# TK104_Pulsbegrenser_Eurorack.net
KiCad netlist of a schematic drawn in Altium Designer
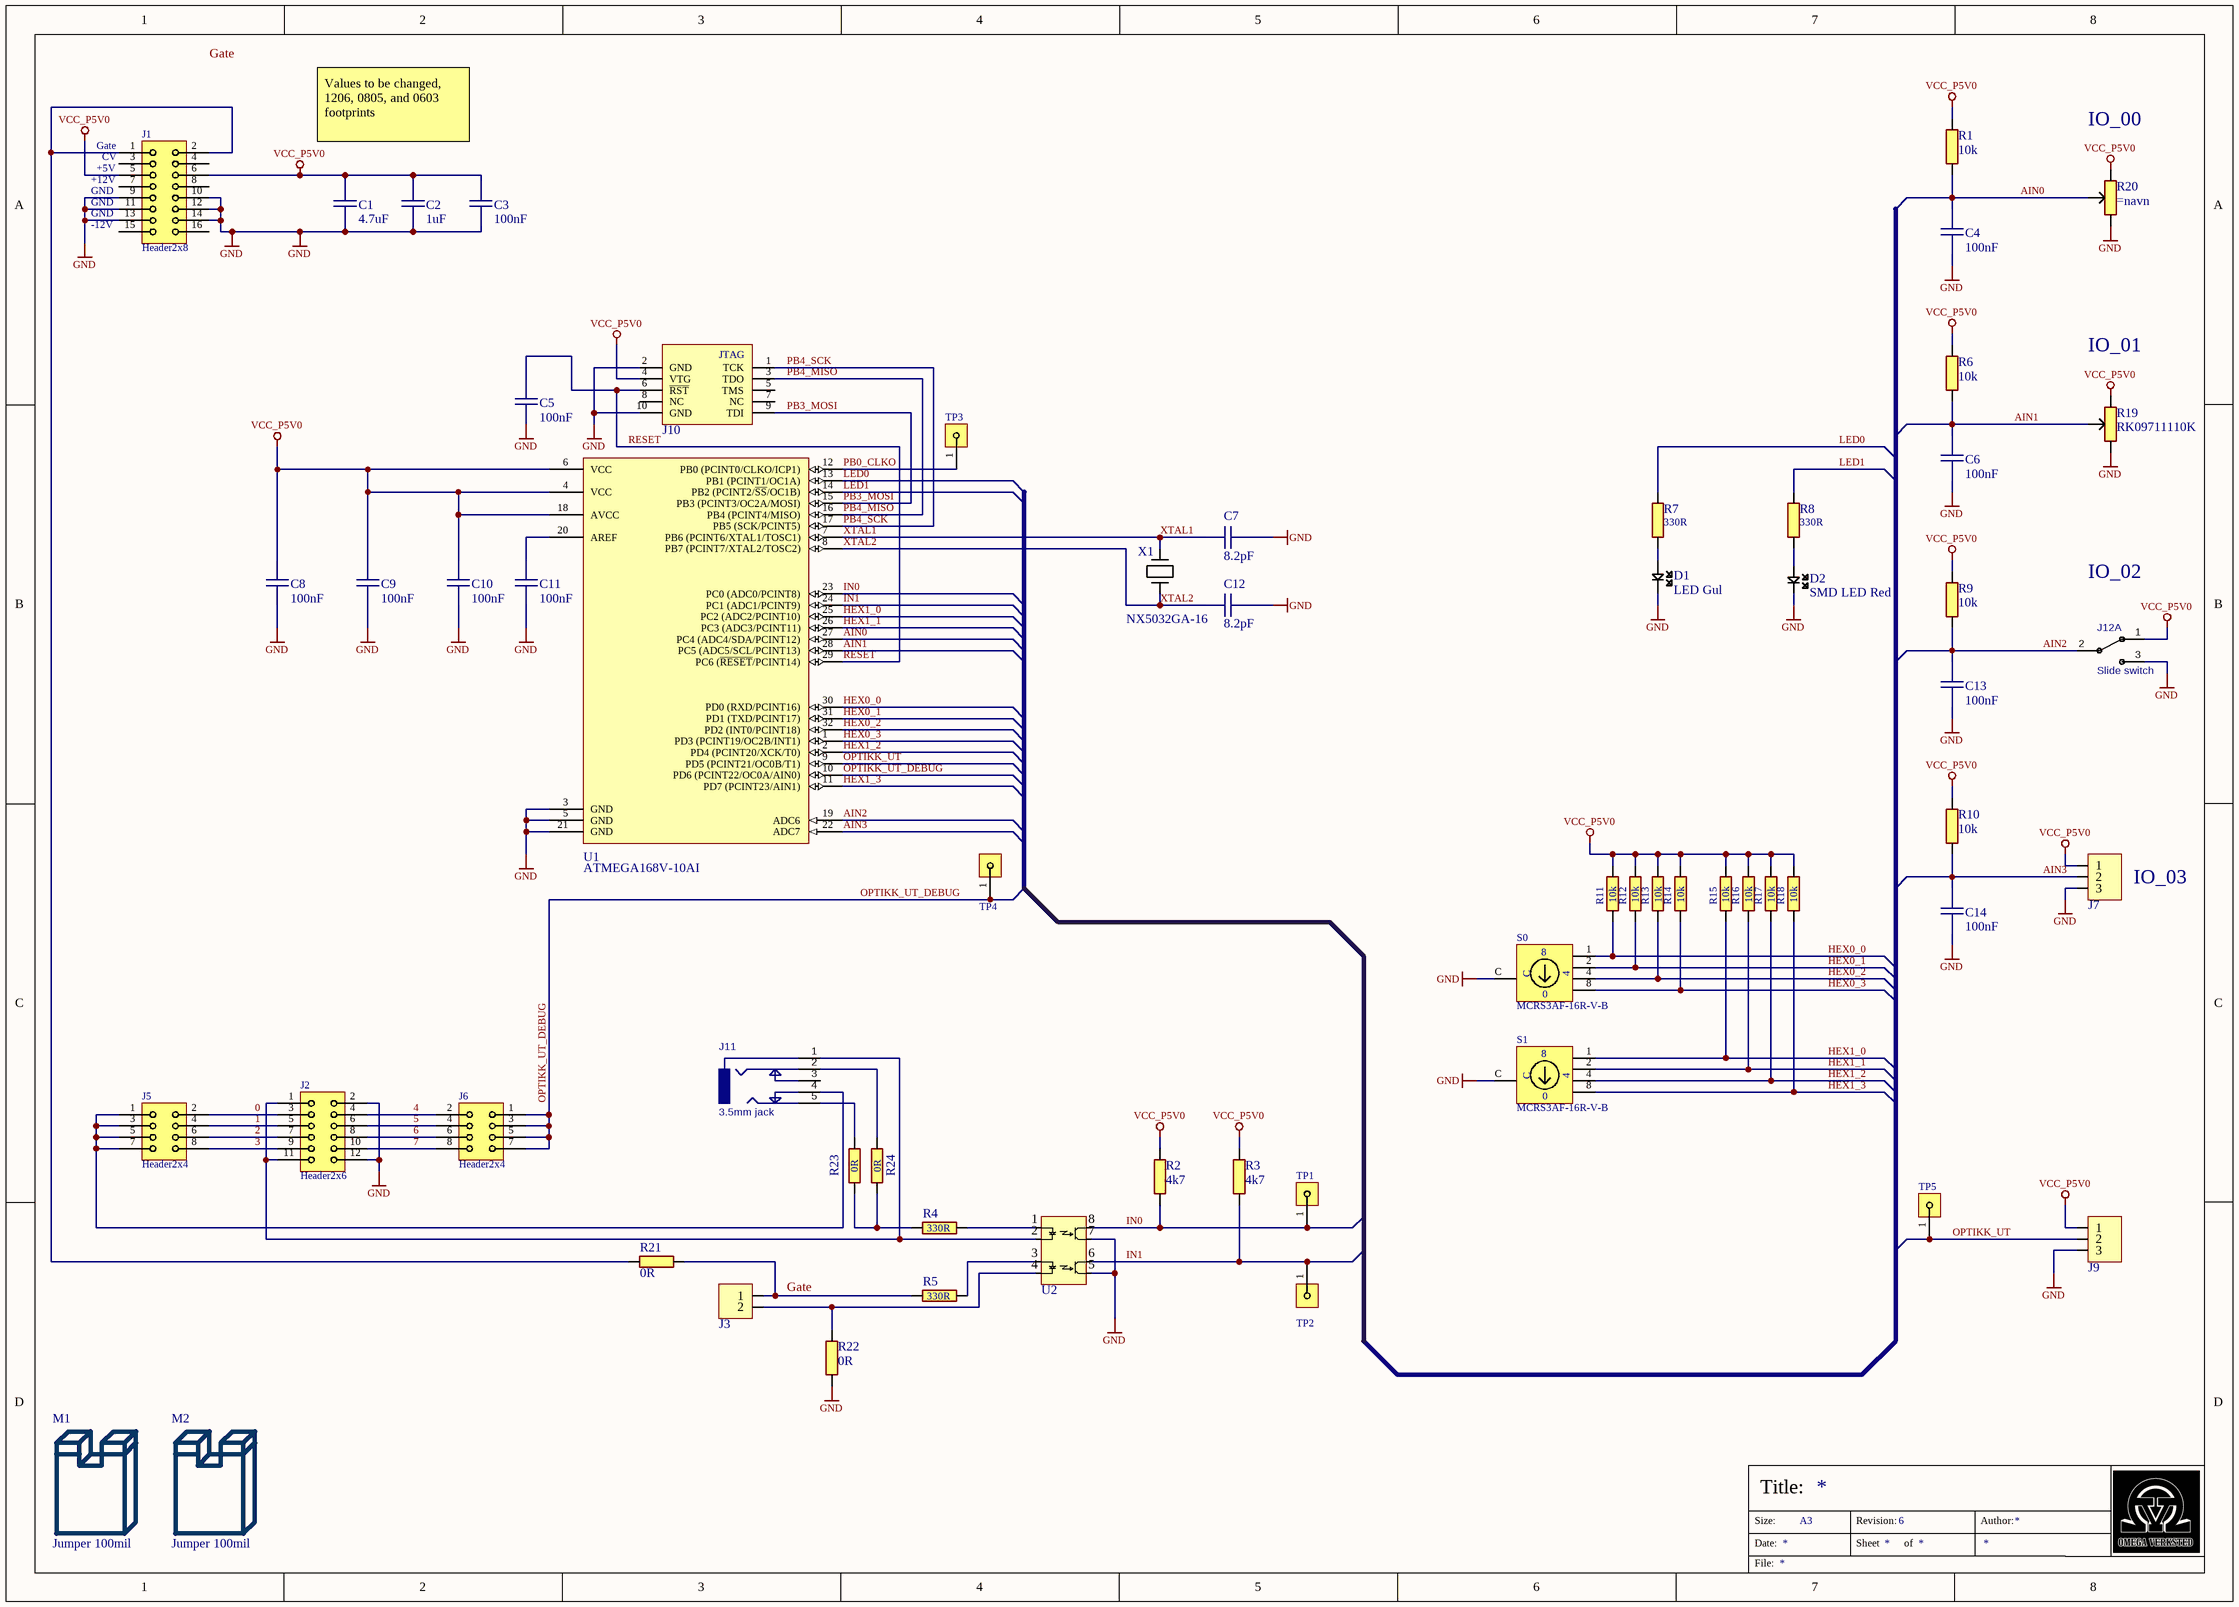
[diagram p0: TK104_Pulsbegrenser_Eurorack.SchDoc]

(export (version "E")
  (design (tool "Eeschema 10.0.6"))
  (components
    (comp (ref "C1")
      (value "4.7uF")
      (footprint "CAPC1206(3216)170_N")
      (description "X7R 50V")
      (libsource (lib "OVLib") (part "CAP"))
    )
    (comp (ref "C2")
      (value "1uF")
      (footprint "CAPC0805(2012)100_N")
      (description "X7R 50V 10%")
      (libsource (lib "OVLib") (part "CAP"))
    )
    (comp (ref "C3")
      (value "100nF")
      (footprint "CAPC0603(1608)55_N")
      (description "X7R 50V 5%")
      (libsource (lib "OVLib") (part "CAP"))
    )
    (comp (ref "C4")
      (value "100nF")
      (footprint "CAPC0603(1608)55_N")
      (description "X7R 50V 5%")
      (libsource (lib "OVLib") (part "CAP"))
    )
    (comp (ref "C5")
      (value "100nF")
      (footprint "CAPC0603(1608)55_N")
      (description "X7R 50V 5%")
      (libsource (lib "OVLib") (part "CAP"))
    )
    (comp (ref "C6")
      (value "100nF")
      (footprint "CAPC0603(1608)55_N")
      (description "X7R 50V 5%")
      (libsource (lib "OVLib") (part "CAP"))
    )
    (comp (ref "C7")
      (value "8.2pF")
      (footprint "CAPC0603(1608)55_N")
      (description "NP0 50V 5%")
      (libsource (lib "OVLib") (part "CAP"))
    )
    (comp (ref "C8")
      (value "100nF")
      (footprint "CAPC0603(1608)55_N")
      (description "X7R 50V 5%")
      (libsource (lib "OVLib") (part "CAP"))
    )
    (comp (ref "C9")
      (value "100nF")
      (footprint "CAPC0603(1608)55_N")
      (description "X7R 50V 5%")
      (libsource (lib "OVLib") (part "CAP"))
    )
    (comp (ref "C10")
      (value "100nF")
      (footprint "CAPC0603(1608)55_N")
      (description "X7R 50V 5%")
      (libsource (lib "OVLib") (part "CAP"))
    )
    (comp (ref "C11")
      (value "100nF")
      (footprint "CAPC0603(1608)55_N")
      (description "X7R 50V 5%")
      (libsource (lib "OVLib") (part "CAP"))
    )
    (comp (ref "C12")
      (value "8.2pF")
      (footprint "CAPC0603(1608)55_N")
      (description "NP0 50V 5%")
      (libsource (lib "OVLib_64") (part "CAP"))
    )
    (comp (ref "C13")
      (value "100nF")
      (footprint "CAPC0603(1608)55_N")
      (description "X7R 50V 5%")
      (libsource (lib "OVLib") (part "CAP"))
    )
    (comp (ref "C14")
      (value "100nF")
      (footprint "CAPC0603(1608)55_N")
      (description "X7R 50V 5%")
      (libsource (lib "OVLib") (part "CAP"))
    )
    (comp (ref "D1")
      (value "LED Gul")
      (footprint "LED254W7L870D500")
      (libsource (lib "OVLib_64") (part "LED"))
    )
    (comp (ref "D2")
      (value "SMD LED Red")
      (footprint "I_LEDC0603(1608)_N")
      (libsource (lib "OVLib") (part "LED"))
    )
    (comp (ref "J1")
      (value "Header2x8")
      (footprint "HDRV16W64P254_2X8_Shrouded")
      (libsource (lib "OVLib_64") (part "Header2x8"))
    )
    (comp (ref "J2")
      (value "Header2x6")
      (footprint "HDRV12W64P254_2X6_RA")
      (libsource (lib "OVLib_64") (part "Header2x6"))
    )
    (comp (ref "J3")
      (value "JST 2pin")
      (footprint "JST_2P")
      (description "pris pr. stk.")
      (libsource (lib "OVLib") (part "2PConnector"))
    )
    (comp (ref "J5")
      (value "Header2x4")
      (footprint "HDRV8W64P254_2X4")
      (libsource (lib "") (part "Header2x4_1"))
    )
    (comp (ref "J6")
      (value "Header2x4")
      (footprint "HDRV8W64P254_2X4")
      (libsource (lib "OVLib_64") (part "Header2x4"))
    )
    (comp (ref "J7")
      (value "JST 3pin")
      (footprint "JST_3P")
      (description "pris pr. stk.")
      (libsource (lib "OVLib") (part "3PConnector"))
    )
    (comp (ref "J9")
      (value "JST 3pin")
      (footprint "JST_3P")
      (description "pris pr. stk.")
      (libsource (lib "OVLib") (part "3PConnector"))
    )
    (comp (ref "J10")
      (value "Header SMD 127 2x5")
      (footprint "SMDHDRV10P127_2X5_615X330X560B")
      (description "1,27mm Pitch SMD Header")
      (libsource (lib "OVLib") (part "AVRJTAG"))
    )
    (comp (ref "J11")
      (value "3.5mm jack")
      (footprint "PJ-306M")
      (description "5-pin 3.5mm 1/8\" Stereo Jack PCB Panel Mount")
      (libsource (lib "OVLib_64") (part "3.5MM_JACK"))
    )
    (comp (ref "J12")
      (value "Slide switch")
      (footprint "1MS1T2B4M7RE")
      (description "Toggle Switch SPDT On-On")
      (libsource (lib "OVLib_64") (part "Slide_switch_DPDT_RA"))
    )
    (comp (ref "M1")
      (value "Jumper 100mil")
      (footprint "SNT-100-BK-T")
      (libsource (lib "OVLib_64") (part "Jumper"))
    )
    (comp (ref "M2")
      (value "Jumper 100mil")
      (footprint "SNT-100-BK-T")
      (libsource (lib "OVLib_64") (part "Jumper"))
    )
    (comp (ref "R1")
      (value "10k")
      (footprint "RESC0603(1608)_N")
      (description "0.1W 1% Thick film resistor")
      (libsource (lib "OVLib") (part "Resistor2"))
    )
    (comp (ref "R2")
      (value "4k7")
      (footprint "RESC0603(1608)_N")
      (description "0.1W 1% Thick film resistor")
      (libsource (lib "OVLib_64") (part "Resistor2"))
    )
    (comp (ref "R3")
      (value "4k7")
      (footprint "RESC0603(1608)_N")
      (description "0.1W 1% Thick film resistor")
      (libsource (lib "OVLib_64") (part "Resistor2"))
    )
    (comp (ref "R4")
      (value "330R")
      (footprint "RESC0603(1608)_N")
      (description "0.1W 1% Thick film resistor")
      (libsource (lib "") (part "Resistor2_1"))
    )
    (comp (ref "R5")
      (value "330R")
      (footprint "RESC0603(1608)_N")
      (description "0.1W 1% Thick film resistor")
      (libsource (lib "") (part "Resistor2_1"))
    )
    (comp (ref "R6")
      (value "10k")
      (footprint "RESC0603(1608)_N")
      (description "0.1W 1% Thick film resistor")
      (libsource (lib "OVLib") (part "Resistor2"))
    )
    (comp (ref "R7")
      (value "330R")
      (footprint "RESC0603(1608)_N")
      (description "0.1W 1% Thick film resistor")
      (libsource (lib "OVLib") (part "Resistor2"))
    )
    (comp (ref "R8")
      (value "330R")
      (footprint "RESC0603(1608)_N")
      (description "0.1W 1% Thick film resistor")
      (libsource (lib "OVLib") (part "Resistor2"))
    )
    (comp (ref "R9")
      (value "10k")
      (footprint "RESC0603(1608)_N")
      (description "0.1W 1% Thick film resistor")
      (libsource (lib "OVLib") (part "Resistor2"))
    )
    (comp (ref "R10")
      (value "10k")
      (footprint "RESC0603(1608)_N")
      (description "0.1W 1% Thick film resistor")
      (libsource (lib "OVLib") (part "Resistor2"))
    )
    (comp (ref "R11")
      (value "10k")
      (footprint "RESC0603(1608)_N")
      (description "0.1W 1% Thick film resistor")
      (libsource (lib "OVLib") (part "Resistor2"))
    )
    (comp (ref "R12")
      (value "10k")
      (footprint "RESC0603(1608)_N")
      (description "0.1W 1% Thick film resistor")
      (libsource (lib "OVLib") (part "Resistor2"))
    )
    (comp (ref "R13")
      (value "10k")
      (footprint "RESC0603(1608)_N")
      (description "0.1W 1% Thick film resistor")
      (libsource (lib "OVLib") (part "Resistor2"))
    )
    (comp (ref "R14")
      (value "10k")
      (footprint "RESC0603(1608)_N")
      (description "0.1W 1% Thick film resistor")
      (libsource (lib "OVLib") (part "Resistor2"))
    )
    (comp (ref "R15")
      (value "10k")
      (footprint "RESC0603(1608)_N")
      (description "0.1W 1% Thick film resistor")
      (libsource (lib "OVLib_64") (part "Resistor2"))
    )
    (comp (ref "R16")
      (value "10k")
      (footprint "RESC0603(1608)_N")
      (description "0.1W 1% Thick film resistor")
      (libsource (lib "OVLib") (part "Resistor2"))
    )
    (comp (ref "R17")
      (value "10k")
      (footprint "RESC0603(1608)_N")
      (description "0.1W 1% Thick film resistor")
      (libsource (lib "OVLib_64") (part "Resistor2"))
    )
    (comp (ref "R18")
      (value "10k")
      (footprint "RESC0603(1608)_N")
      (description "0.1W 1% Thick film resistor")
      (libsource (lib "OVLib_64") (part "Resistor2"))
    )
    (comp (ref "R19")
      (value "RK09711110K")
      (footprint "RK09711110K")
      (description "10k linear pot 1 turn")
      (libsource (lib "OVLib_64") (part "Potmeter"))
    )
    (comp (ref "R20") (value "~") (footprint "PTA4543-ANGLE") (libsource (lib "Potmeter") (part "Potmeter")))
    (comp (ref "R21")
      (value "0R")
      (footprint "RESC0603(1608)_N")
      (description "0.1W 1% Thick film resistor")
      (libsource (lib "") (part "Resistor2_1"))
    )
    (comp (ref "R22")
      (value "0R")
      (footprint "RESC0603(1608)_N")
      (description "0.1W 1% Thick film resistor")
      (libsource (lib "OVLib_64") (part "Resistor2"))
    )
    (comp (ref "R23")
      (value "0R")
      (footprint "RESC0603(1608)_N")
      (description "0.1W 1% Thick film resistor")
      (libsource (lib "OVLib_64") (part "Resistor2"))
    )
    (comp (ref "R24")
      (value "0R")
      (footprint "RESC0603(1608)_N")
      (description "0.1W 1% Thick film resistor")
      (libsource (lib "OVLib_64") (part "Resistor2"))
    )
    (comp (ref "S0")
      (value "MCRS3AF-16R-V-B")
      (footprint "MCRS3AF-16R-V-B")
      (description "Rotary hex switch")
      (libsource (lib "OVLib_64") (part "Hex_switch"))
    )
    (comp (ref "S1")
      (value "MCRS3AF-16R-V-B")
      (footprint "MCRS3AF-16R-V-B")
      (description "Rotary hex switch")
      (libsource (lib "OVLib_64") (part "Hex_switch"))
    )
    (comp (ref "TP1")
      (value "Header1x1")
      (footprint "HDRV1W64P254_1X1_254X254X900B")
      (libsource (lib "OVLib") (part "Header1x1"))
    )
    (comp (ref "TP2")
      (value "Header1x1")
      (footprint "HDRV1W64P254_1X1_254X254X900B")
      (libsource (lib "") (part "Header1x1_1"))
    )
    (comp (ref "TP3")
      (value "Header1x1")
      (footprint "HDRV1W64P254_1X1_254X254X900B")
      (libsource (lib "OVLib") (part "Header1x1"))
    )
    (comp (ref "TP4")
      (value "Header1x1")
      (footprint "HDRV1W64P254_1X1_254X254X900B")
      (libsource (lib "") (part "Header1x1_2"))
    )
    (comp (ref "TP5")
      (value "Header1x1")
      (footprint "HDRV1W64P254_1X1_254X254X900B")
      (libsource (lib "OVLib") (part "Header1x1"))
    )
    (comp (ref "U1")
      (value "ATMEGA168V-10AI")
      (footprint "TQFP80P900X900X120-32N")
      (libsource (lib "OVLib") (part "ATMEGA168V"))
    )
    (comp (ref "U2")
      (value "Dual_Optocoupler")
      (footprint "SOIC127P590X363-8N")
      (description "Dual Optocoupler")
      (libsource (lib "OVLib") (part "Dual_Optocoupler"))
    )
    (comp (ref "X1")
      (value "NX5032GA-16")
      (footprint "CRYSTAL-ABM7")
      (description "Crystal 16 MHz")
      (libsource (lib "OVLib") (part "GENERIC-CRYSTAL"))
    )
  )
  (nets
    (net (code "1") (name "/0") (class "Default")
      (node (ref "J2") (pin "3") (pinfunction "3_3") (pintype "passive"))
      (node (ref "J5") (pin "2") (pinfunction "2_2") (pintype "passive"))
    )
    (net (code "2") (name "/1") (class "Default")
      (node (ref "J2") (pin "5") (pinfunction "5_5") (pintype "passive"))
      (node (ref "J5") (pin "4") (pinfunction "4_4") (pintype "passive"))
    )
    (net (code "3") (name "/2") (class "Default")
      (node (ref "J2") (pin "7") (pinfunction "7_7") (pintype "passive"))
      (node (ref "J5") (pin "6") (pinfunction "6_6") (pintype "passive"))
    )
    (net (code "4") (name "/3") (class "Default")
      (node (ref "J2") (pin "9") (pinfunction "9_9") (pintype "passive"))
      (node (ref "J5") (pin "8") (pinfunction "8_8") (pintype "passive"))
    )
    (net (code "5") (name "/4") (class "Default")
      (node (ref "J2") (pin "4") (pinfunction "4_4") (pintype "passive"))
      (node (ref "J6") (pin "2") (pinfunction "2_2") (pintype "passive"))
    )
    (net (code "6") (name "/5") (class "Default")
      (node (ref "J2") (pin "6") (pinfunction "6_6") (pintype "passive"))
      (node (ref "J6") (pin "4") (pinfunction "4_4") (pintype "passive"))
    )
    (net (code "7") (name "/6") (class "Default")
      (node (ref "J2") (pin "8") (pinfunction "8_8") (pintype "passive"))
      (node (ref "J6") (pin "6") (pinfunction "6_6") (pintype "passive"))
    )
    (net (code "8") (name "/7") (class "Default")
      (node (ref "J2") (pin "10") (pinfunction "10_10") (pintype "passive"))
      (node (ref "J6") (pin "8") (pinfunction "8_8") (pintype "passive"))
    )
    (net (code "9") (name "/AIN0") (class "Default")
      (node (ref "C4") (pin "2") (pinfunction "2_2") (pintype "passive"))
      (node (ref "R1") (pin "1") (pinfunction "1_1") (pintype "passive"))
      (node (ref "R20") (pin "2") (pinfunction "2_2") (pintype "passive"))
      (node (ref "U1") (pin "27") (pinfunction "PC4_(ADC4/SDA/PCINT12)_27") (pintype "bidirectional"))
    )
    (net (code "10") (name "/AIN1") (class "Default")
      (node (ref "C6") (pin "2") (pinfunction "2_2") (pintype "passive"))
      (node (ref "R19") (pin "2") (pinfunction "2_2") (pintype "passive"))
      (node (ref "R6") (pin "1") (pinfunction "1_1") (pintype "passive"))
      (node (ref "U1") (pin "28") (pinfunction "PC5_(ADC5/SCL/PCINT13)_28") (pintype "bidirectional"))
    )
    (net (code "11") (name "/AIN2") (class "Default")
      (node (ref "C13") (pin "2") (pinfunction "2_2") (pintype "passive"))
      (node (ref "J12") (pin "2") (pinfunction "2_2") (pintype "passive"))
      (node (ref "R9") (pin "1") (pinfunction "1_1") (pintype "passive"))
      (node (ref "U1") (pin "19") (pinfunction "ADC6_19") (pintype "input"))
    )
    (net (code "12") (name "/AIN3") (class "Default")
      (node (ref "C14") (pin "2") (pinfunction "2_2") (pintype "passive"))
      (node (ref "J7") (pin "2") (pinfunction "2_2") (pintype "passive"))
      (node (ref "R10") (pin "1") (pinfunction "1_1") (pintype "passive"))
      (node (ref "U1") (pin "22") (pinfunction "ADC7_22") (pintype "input"))
    )
    (net (code "13") (name "/Gate") (class "Default")
      (node (ref "J3") (pin "1") (pinfunction "1_1") (pintype "passive"))
      (node (ref "R21") (pin "2") (pinfunction "2_2") (pintype "passive"))
      (node (ref "R5") (pin "1") (pinfunction "1_1") (pintype "passive"))
    )
    (net (code "14") (name "/HEX0_0") (class "Default")
      (node (ref "R11") (pin "1") (pinfunction "1_1") (pintype "passive"))
      (node (ref "S0") (pin "1") (pinfunction "1_1") (pintype "passive"))
      (node (ref "U1") (pin "30") (pinfunction "PD0_(RXD/PCINT16)_30") (pintype "bidirectional"))
    )
    (net (code "15") (name "/HEX0_1") (class "Default")
      (node (ref "R12") (pin "1") (pinfunction "1_1") (pintype "passive"))
      (node (ref "S0") (pin "2") (pinfunction "2_2") (pintype "passive"))
      (node (ref "U1") (pin "31") (pinfunction "PD1_(TXD/PCINT17)_31") (pintype "bidirectional"))
    )
    (net (code "16") (name "/HEX0_2") (class "Default")
      (node (ref "R13") (pin "1") (pinfunction "1_1") (pintype "passive"))
      (node (ref "S0") (pin "4") (pinfunction "4_4") (pintype "passive"))
      (node (ref "U1") (pin "32") (pinfunction "PD2_(INT0/PCINT18)_32") (pintype "bidirectional"))
    )
    (net (code "17") (name "/HEX0_3") (class "Default")
      (node (ref "R14") (pin "1") (pinfunction "1_1") (pintype "passive"))
      (node (ref "S0") (pin "8") (pinfunction "8_8") (pintype "passive"))
      (node (ref "U1") (pin "1") (pinfunction "PD3_(PCINT19/OC2B/INT1)_1") (pintype "bidirectional"))
    )
    (net (code "18") (name "/HEX1_0") (class "Default")
      (node (ref "R15") (pin "1") (pinfunction "1_1") (pintype "passive"))
      (node (ref "S1") (pin "1") (pinfunction "1_1") (pintype "passive"))
      (node (ref "U1") (pin "25") (pinfunction "PC2_(ADC2/PCINT10)_25") (pintype "bidirectional"))
    )
    (net (code "19") (name "/HEX1_1") (class "Default")
      (node (ref "R16") (pin "1") (pinfunction "1_1") (pintype "passive"))
      (node (ref "S1") (pin "2") (pinfunction "2_2") (pintype "passive"))
      (node (ref "U1") (pin "26") (pinfunction "PC3_(ADC3/PCINT11)_26") (pintype "bidirectional"))
    )
    (net (code "20") (name "/HEX1_2") (class "Default")
      (node (ref "R17") (pin "1") (pinfunction "1_1") (pintype "passive"))
      (node (ref "S1") (pin "4") (pinfunction "4_4") (pintype "passive"))
      (node (ref "U1") (pin "2") (pinfunction "PD4_(PCINT20/XCK/T0)_2") (pintype "bidirectional"))
    )
    (net (code "21") (name "/HEX1_3") (class "Default")
      (node (ref "R18") (pin "1") (pinfunction "1_1") (pintype "passive"))
      (node (ref "S1") (pin "8") (pinfunction "8_8") (pintype "passive"))
      (node (ref "U1") (pin "11") (pinfunction "PD7_(PCINT23/AIN1)_11") (pintype "bidirectional"))
    )
    (net (code "22") (name "/IN0") (class "Default")
      (node (ref "R2") (pin "1") (pinfunction "1_1") (pintype "passive"))
      (node (ref "TP1") (pin "1") (pinfunction "1_1") (pintype "passive"))
      (node (ref "U1") (pin "23") (pinfunction "PC0_(ADC0/PCINT8)_23") (pintype "bidirectional"))
      (node (ref "U2") (pin "8") (pinfunction "8_8") (pintype "passive"))
    )
    (net (code "23") (name "/IN1") (class "Default")
      (node (ref "R3") (pin "1") (pinfunction "1_1") (pintype "passive"))
      (node (ref "TP2") (pin "1") (pinfunction "1_1") (pintype "passive"))
      (node (ref "U1") (pin "24") (pinfunction "PC1_(ADC1/PCINT9)_24") (pintype "bidirectional"))
      (node (ref "U2") (pin "6") (pinfunction "6_6") (pintype "passive"))
    )
    (net (code "24") (name "/LED0") (class "Default")
      (node (ref "R7") (pin "2") (pinfunction "2_2") (pintype "passive"))
      (node (ref "U1") (pin "13") (pinfunction "PB1_(PCINT1/OC1A)_13") (pintype "bidirectional"))
    )
    (net (code "25") (name "/LED1") (class "Default")
      (node (ref "R8") (pin "2") (pinfunction "2_2") (pintype "passive"))
      (node (ref "U1") (pin "14") (pinfunction "PB2_(PCINT2/~{SS}/OC1B)_14") (pintype "bidirectional"))
    )
    (net (code "26") (name "/OPTIKK_UT") (class "Default")
      (node (ref "J9") (pin "2") (pinfunction "2_2") (pintype "passive"))
      (node (ref "TP5") (pin "1") (pinfunction "1_1") (pintype "passive"))
      (node (ref "U1") (pin "9") (pinfunction "PD5_(PCINT21/OC0B/T1)_9") (pintype "bidirectional"))
    )
    (net (code "27") (name "/OPTIKK_UT_DEBUG") (class "Default")
      (node (ref "J6") (pin "1") (pinfunction "1_1") (pintype "passive"))
      (node (ref "J6") (pin "3") (pinfunction "3_3") (pintype "passive"))
      (node (ref "J6") (pin "5") (pinfunction "5_5") (pintype "passive"))
      (node (ref "J6") (pin "7") (pinfunction "7_7") (pintype "passive"))
      (node (ref "TP4") (pin "1") (pinfunction "1_1") (pintype "passive"))
      (node (ref "U1") (pin "10") (pinfunction "PD6_(PCINT22/OC0A/AIN0)_10") (pintype "bidirectional"))
    )
    (net (code "28") (name "/PB0_CLKO") (class "Default")
      (node (ref "TP3") (pin "1") (pinfunction "1_1") (pintype "passive"))
      (node (ref "U1") (pin "12") (pinfunction "PB0_(PCINT0/CLKO/ICP1)_12") (pintype "bidirectional"))
    )
    (net (code "29") (name "/PB3_MOSI") (class "Default")
      (node (ref "J10") (pin "9") (pinfunction "TDI_9") (pintype "passive"))
      (node (ref "U1") (pin "15") (pinfunction "PB3_(PCINT3/OC2A/MOSI)_15") (pintype "bidirectional"))
    )
    (net (code "30") (name "/PB4_MISO") (class "Default")
      (node (ref "J10") (pin "3") (pinfunction "TDO_3") (pintype "passive"))
      (node (ref "U1") (pin "16") (pinfunction "PB4_(PCINT4/MISO)_16") (pintype "bidirectional"))
    )
    (net (code "31") (name "/PB4_SCK") (class "Default")
      (node (ref "J10") (pin "1") (pinfunction "TCK_1") (pintype "passive"))
      (node (ref "U1") (pin "17") (pinfunction "PB5_(SCK/PCINT5)_17") (pintype "bidirectional"))
    )
    (net (code "32") (name "/RESET") (class "Default")
      (node (ref "C5") (pin "2") (pinfunction "2_2") (pintype "passive"))
      (node (ref "J10") (pin "6") (pinfunction "~{RST}_6") (pintype "passive"))
      (node (ref "U1") (pin "29") (pinfunction "PC6_(~{RESET}/PCINT14)_29") (pintype "bidirectional"))
    )
    (net (code "33") (name "/XTAL1") (class "Default")
      (node (ref "C7") (pin "2") (pinfunction "2_2") (pintype "passive"))
      (node (ref "U1") (pin "7") (pinfunction "PB6_(PCINT6/XTAL1/TOSC1)_7") (pintype "bidirectional"))
      (node (ref "X1") (pin "1") (pintype "passive"))
    )
    (net (code "34") (name "/XTAL2") (class "Default")
      (node (ref "C12") (pin "2") (pinfunction "2_2") (pintype "passive"))
      (node (ref "U1") (pin "8") (pinfunction "PB7_(PCINT7/XTAL2/TOSC2)_8") (pintype "bidirectional"))
      (node (ref "X1") (pin "2") (pintype "passive"))
    )
    (net (code "35") (name "GND") (class "Default")
      (node (ref "C1") (pin "1") (pinfunction "1_1") (pintype "passive"))
      (node (ref "C10") (pin "1") (pinfunction "1_1") (pintype "passive"))
      (node (ref "C11") (pin "1") (pinfunction "1_1") (pintype "passive"))
      (node (ref "C12") (pin "1") (pinfunction "1_1") (pintype "passive"))
      (node (ref "C13") (pin "1") (pinfunction "1_1") (pintype "passive"))
      (node (ref "C14") (pin "1") (pinfunction "1_1") (pintype "passive"))
      (node (ref "C2") (pin "1") (pinfunction "1_1") (pintype "passive"))
      (node (ref "C3") (pin "1") (pinfunction "1_1") (pintype "passive"))
      (node (ref "C4") (pin "1") (pinfunction "1_1") (pintype "passive"))
      (node (ref "C5") (pin "1") (pinfunction "1_1") (pintype "passive"))
      (node (ref "C6") (pin "1") (pinfunction "1_1") (pintype "passive"))
      (node (ref "C7") (pin "1") (pinfunction "1_1") (pintype "passive"))
      (node (ref "C8") (pin "2") (pinfunction "2_2") (pintype "passive"))
      (node (ref "C9") (pin "2") (pinfunction "2_2") (pintype "passive"))
      (node (ref "D1") (pin "2") (pinfunction "2_2") (pintype "passive"))
      (node (ref "D2") (pin "2") (pinfunction "2_2") (pintype "passive"))
      (node (ref "J1") (pin "10") (pinfunction "10_10") (pintype "passive"))
      (node (ref "J1") (pin "11") (pinfunction "11_11") (pintype "passive"))
      (node (ref "J1") (pin "12") (pinfunction "12_12") (pintype "passive"))
      (node (ref "J1") (pin "13") (pinfunction "13_13") (pintype "passive"))
      (node (ref "J1") (pin "14") (pinfunction "14_14") (pintype "passive"))
      (node (ref "J1") (pin "9") (pinfunction "9_9") (pintype "passive"))
      (node (ref "J10") (pin "10") (pinfunction "GND_10") (pintype "passive"))
      (node (ref "J10") (pin "2") (pinfunction "GND_2") (pintype "passive"))
      (node (ref "J12") (pin "3") (pinfunction "3_3") (pintype "passive"))
      (node (ref "J2") (pin "12") (pinfunction "12_12") (pintype "passive"))
      (node (ref "J2") (pin "2") (pinfunction "2_2") (pintype "passive"))
      (node (ref "J7") (pin "3") (pinfunction "3_3") (pintype "passive"))
      (node (ref "J9") (pin "3") (pinfunction "3_3") (pintype "passive"))
      (node (ref "R19") (pin "1") (pinfunction "1_1") (pintype "passive"))
      (node (ref "R20") (pin "3") (pinfunction "3_3") (pintype "passive"))
      (node (ref "R22") (pin "1") (pinfunction "1_1") (pintype "passive"))
      (node (ref "S0") (pin "C") (pinfunction "C_C") (pintype "passive"))
      (node (ref "S1") (pin "C") (pinfunction "C_C") (pintype "passive"))
      (node (ref "U1") (pin "21") (pinfunction "GND_21") (pintype "power_in"))
      (node (ref "U1") (pin "3") (pinfunction "GND_3") (pintype "power_in"))
      (node (ref "U1") (pin "5") (pinfunction "GND_5") (pintype "power_in"))
      (node (ref "U2") (pin "5") (pinfunction "5_5") (pintype "passive"))
      (node (ref "U2") (pin "7") (pinfunction "7_7") (pintype "passive"))
    )
    (net (code "36") (name "Net-(D1-Pad1)") (class "Default")
      (node (ref "D1") (pin "1") (pinfunction "1_1") (pintype "passive"))
      (node (ref "R7") (pin "1") (pinfunction "1_1") (pintype "passive"))
    )
    (net (code "37") (name "Net-(D2-Pad1)") (class "Default")
      (node (ref "D2") (pin "1") (pinfunction "1_1") (pintype "passive"))
      (node (ref "R8") (pin "1") (pinfunction "1_1") (pintype "passive"))
    )
    (net (code "38") (name "Net-(J1-Pad1)") (class "Default")
      (node (ref "J1") (pin "1") (pinfunction "1_1") (pintype "passive"))
      (node (ref "J1") (pin "2") (pinfunction "2_2") (pintype "passive"))
      (node (ref "R21") (pin "1") (pinfunction "1_1") (pintype "passive"))
    )
    (net (code "39") (name "Net-(J3-Pad2)") (class "Default")
      (node (ref "J3") (pin "2") (pinfunction "2_2") (pintype "passive"))
      (node (ref "R22") (pin "2") (pinfunction "2_2") (pintype "passive"))
      (node (ref "U2") (pin "4") (pinfunction "4_4") (pintype "passive"))
    )
    (net (code "40") (name "Net-(J11-Pad1)") (class "Default")
      (node (ref "J11") (pin "1") (pinfunction "1_1") (pintype "passive"))
      (node (ref "J2") (pin "1") (pinfunction "1_1") (pintype "passive"))
      (node (ref "J2") (pin "11") (pinfunction "11_11") (pintype "passive"))
      (node (ref "U2") (pin "2") (pinfunction "2_2") (pintype "passive"))
    )
    (net (code "41") (name "Net-(J11-Pad2)") (class "Default")
      (node (ref "J11") (pin "2") (pinfunction "2_2") (pintype "passive"))
      (node (ref "R24") (pin "2") (pinfunction "2_2") (pintype "passive"))
    )
    (net (code "42") (name "Net-(J11-Pad4)") (class "Default")
      (node (ref "J11") (pin "4") (pinfunction "4_4") (pintype "passive"))
      (node (ref "J5") (pin "1") (pinfunction "1_1") (pintype "passive"))
      (node (ref "J5") (pin "3") (pinfunction "3_3") (pintype "passive"))
      (node (ref "J5") (pin "5") (pinfunction "5_5") (pintype "passive"))
      (node (ref "J5") (pin "7") (pinfunction "7_7") (pintype "passive"))
    )
    (net (code "43") (name "Net-(J11-Pad5)") (class "Default")
      (node (ref "J11") (pin "5") (pinfunction "5_5") (pintype "passive"))
      (node (ref "R23") (pin "2") (pinfunction "2_2") (pintype "passive"))
    )
    (net (code "44") (name "Net-(R4-Pad2)") (class "Default")
      (node (ref "R4") (pin "2") (pinfunction "2_2") (pintype "passive"))
      (node (ref "U2") (pin "1") (pinfunction "1_1") (pintype "passive"))
    )
    (net (code "45") (name "Net-(R5-Pad2)") (class "Default")
      (node (ref "R5") (pin "2") (pinfunction "2_2") (pintype "passive"))
      (node (ref "U2") (pin "3") (pinfunction "3_3") (pintype "passive"))
    )
    (net (code "46") (name "Net-(R23-Pad1)") (class "Default")
      (node (ref "R23") (pin "1") (pinfunction "1_1") (pintype "passive"))
      (node (ref "R24") (pin "1") (pinfunction "1_1") (pintype "passive"))
      (node (ref "R4") (pin "1") (pinfunction "1_1") (pintype "passive"))
    )
    (net (code "47") (name "Net-(U1-AREF)") (class "Default")
      (node (ref "C11") (pin "2") (pinfunction "2_2") (pintype "passive"))
      (node (ref "U1") (pin "20") (pinfunction "AREF_20") (pintype "passive"))
    )
    (net (code "48") (name "VCC_P5V0") (class "Default")
      (node (ref "C1") (pin "2") (pinfunction "2_2") (pintype "passive"))
      (node (ref "C10") (pin "2") (pinfunction "2_2") (pintype "passive"))
      (node (ref "C2") (pin "2") (pinfunction "2_2") (pintype "passive"))
      (node (ref "C3") (pin "2") (pinfunction "2_2") (pintype "passive"))
      (node (ref "C8") (pin "1") (pinfunction "1_1") (pintype "passive"))
      (node (ref "C9") (pin "1") (pinfunction "1_1") (pintype "passive"))
      (node (ref "J1") (pin "5") (pinfunction "5_5") (pintype "passive"))
      (node (ref "J1") (pin "6") (pinfunction "6_6") (pintype "passive"))
      (node (ref "J10") (pin "4") (pinfunction "VTG_4") (pintype "passive"))
      (node (ref "J12") (pin "1") (pinfunction "1_1") (pintype "passive"))
      (node (ref "J7") (pin "1") (pinfunction "1_1") (pintype "passive"))
      (node (ref "J9") (pin "1") (pinfunction "1_1") (pintype "passive"))
      (node (ref "R1") (pin "2") (pinfunction "2_2") (pintype "passive"))
      (node (ref "R10") (pin "2") (pinfunction "2_2") (pintype "passive"))
      (node (ref "R11") (pin "2") (pinfunction "2_2") (pintype "passive"))
      (node (ref "R12") (pin "2") (pinfunction "2_2") (pintype "passive"))
      (node (ref "R13") (pin "2") (pinfunction "2_2") (pintype "passive"))
      (node (ref "R14") (pin "2") (pinfunction "2_2") (pintype "passive"))
      (node (ref "R15") (pin "2") (pinfunction "2_2") (pintype "passive"))
      (node (ref "R16") (pin "2") (pinfunction "2_2") (pintype "passive"))
      (node (ref "R17") (pin "2") (pinfunction "2_2") (pintype "passive"))
      (node (ref "R18") (pin "2") (pinfunction "2_2") (pintype "passive"))
      (node (ref "R19") (pin "3") (pinfunction "3_3") (pintype "passive"))
      (node (ref "R2") (pin "2") (pinfunction "2_2") (pintype "passive"))
      (node (ref "R20") (pin "1") (pinfunction "1_1") (pintype "passive"))
      (node (ref "R3") (pin "2") (pinfunction "2_2") (pintype "passive"))
      (node (ref "R6") (pin "2") (pinfunction "2_2") (pintype "passive"))
      (node (ref "R9") (pin "2") (pinfunction "2_2") (pintype "passive"))
      (node (ref "U1") (pin "18") (pinfunction "AVCC_18") (pintype "power_in"))
      (node (ref "U1") (pin "4") (pinfunction "VCC_4") (pintype "power_in"))
      (node (ref "U1") (pin "6") (pinfunction "VCC_6") (pintype "power_in"))
    )
    (net (code "49") (name "unconnected-(J1-Pad3)") (class "Default")
      (node (ref "J1") (pin "3") (pinfunction "3_3") (pintype "passive"))
    )
    (net (code "50") (name "unconnected-(J1-Pad4)") (class "Default")
      (node (ref "J1") (pin "4") (pinfunction "4_4") (pintype "passive"))
    )
    (net (code "51") (name "unconnected-(J1-Pad7)") (class "Default")
      (node (ref "J1") (pin "7") (pinfunction "7_7") (pintype "passive"))
    )
    (net (code "52") (name "unconnected-(J1-Pad8)") (class "Default")
      (node (ref "J1") (pin "8") (pinfunction "8_8") (pintype "passive"))
    )
    (net (code "53") (name "unconnected-(J1-Pad15)") (class "Default")
      (node (ref "J1") (pin "15") (pinfunction "15_15") (pintype "passive"))
    )
    (net (code "54") (name "unconnected-(J1-Pad16)") (class "Default")
      (node (ref "J1") (pin "16") (pinfunction "16_16") (pintype "passive"))
    )
    (net (code "55") (name "unconnected-(J10-NC-Pad7)") (class "Default")
      (node (ref "J10") (pin "7") (pinfunction "NC_7") (pintype "passive"))
    )
    (net (code "56") (name "unconnected-(J10-NC-Pad8)") (class "Default")
      (node (ref "J10") (pin "8") (pinfunction "NC_8") (pintype "passive"))
    )
    (net (code "57") (name "unconnected-(J10-TMS-Pad5)") (class "Default")
      (node (ref "J10") (pin "5") (pinfunction "TMS_5") (pintype "passive"))
    )
    (net (code "58") (name "unconnected-(J11-Pad3)") (class "Default")
      (node (ref "J11") (pin "3") (pinfunction "3_3") (pintype "passive"))
    )
  )
)
